# rc_switch_dualsided.net
KiCad netlist of a schematic drawn in EAGLE
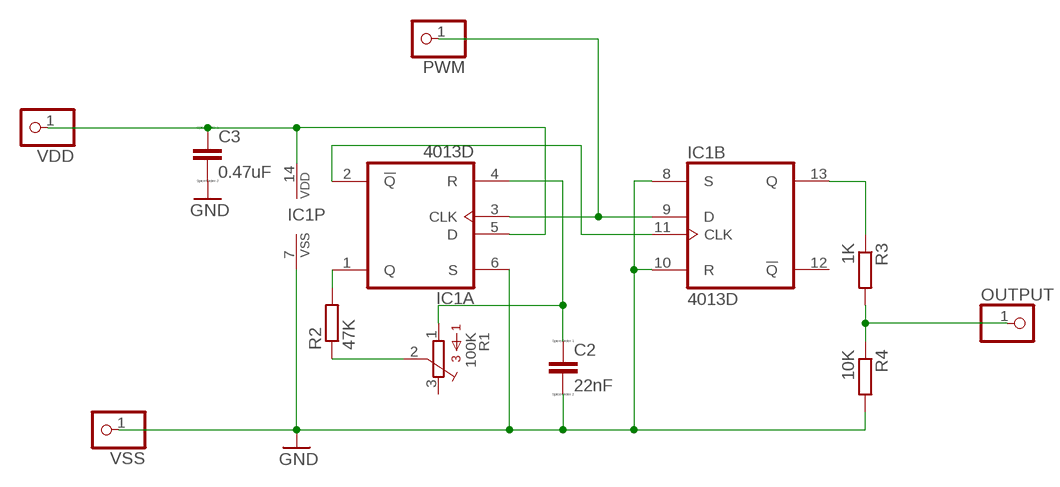
[diagram p0: schematic, sheet 1]

(export (version "E")
  (design (tool "Eeschema 10.0.6"))
  (components
    (comp (ref "C2")
      (value "22nF")
      (footprint "eagle-import:C3216")
      (libsource (lib "eagle-import") (part "CC3216"))
    )
    (comp (ref "C3")
      (value "0.47uF")
      (footprint "eagle-import:C3216")
      (libsource (lib "eagle-import") (part "CC3216"))
    )
    (comp (ref "IC1")
      (value "4013D")
      (footprint "eagle-import:SO14")
      (libsource (lib "eagle-import") (part "4013D"))
    )
    (comp (ref "OUTPUT")
      (value "PINHD-1X1")
      (footprint "eagle-import:1X01")
      (libsource (lib "eagle-import") (part "PINHD-1X1"))
    )
    (comp (ref "PWM")
      (value "PINHD-1X1")
      (footprint "eagle-import:1X01")
      (libsource (lib "eagle-import") (part "PINHD-1X1"))
    )
    (comp (ref "R1")
      (value "100K")
      (footprint "eagle-import:3386P")
      (libsource (lib "eagle-import") (part "3386-P"))
    )
    (comp (ref "R2")
      (value "47K")
      (footprint "eagle-import:R3225")
      (libsource (lib "eagle-import") (part "R-EU_R3225"))
    )
    (comp (ref "R3")
      (value "1K")
      (footprint "eagle-import:R3225")
      (libsource (lib "eagle-import") (part "R-EU_R3225"))
    )
    (comp (ref "R4")
      (value "10K")
      (footprint "eagle-import:R3225")
      (libsource (lib "eagle-import") (part "R-EU_R3225"))
    )
    (comp (ref "VDD")
      (value "PINHD-1X1")
      (footprint "eagle-import:1X01")
      (libsource (lib "eagle-import") (part "PINHD-1X1"))
    )
    (comp (ref "VSS")
      (value "PINHD-1X1")
      (footprint "eagle-import:1X01")
      (libsource (lib "eagle-import") (part "PINHD-1X1"))
    )
  )
  (nets
    (net (code "1") (name "GND") (class "Default")
      (node (ref "C2") (pin "2") (pinfunction "2_2") (pintype "passive"))
      (node (ref "C3") (pin "2") (pinfunction "2_2") (pintype "passive"))
      (node (ref "IC1") (pin "10") (pinfunction "R_10") (pintype "input"))
      (node (ref "IC1") (pin "6") (pinfunction "S_6") (pintype "input"))
      (node (ref "IC1") (pin "7") (pinfunction "VSS_7") (pintype "power_in"))
      (node (ref "IC1") (pin "8") (pinfunction "S_8") (pintype "input"))
      (node (ref "R4") (pin "2") (pinfunction "2_2") (pintype "passive"))
      (node (ref "VSS") (pin "1") (pinfunction "1_1") (pintype "passive"))
    )
    (net (code "2") (name "Net-(IC1A-CLK)") (class "Default")
      (node (ref "IC1") (pin "3") (pinfunction "CLK_3") (pintype "input"))
      (node (ref "IC1") (pin "9") (pinfunction "D_9") (pintype "input"))
      (node (ref "PWM") (pin "1") (pinfunction "1_1") (pintype "passive"))
    )
    (net (code "3") (name "Net-(IC1A-D)") (class "Default")
      (node (ref "C3") (pin "1") (pinfunction "1_1") (pintype "passive"))
      (node (ref "IC1") (pin "14") (pinfunction "VDD_14") (pintype "power_in"))
      (node (ref "IC1") (pin "5") (pinfunction "D_5") (pintype "input"))
      (node (ref "VDD") (pin "1") (pinfunction "1_1") (pintype "passive"))
    )
    (net (code "4") (name "Net-(IC1A-Q)") (class "Default")
      (node (ref "IC1") (pin "1") (pinfunction "Q_1") (pintype "output"))
      (node (ref "R2") (pin "2") (pinfunction "2_2") (pintype "passive"))
    )
    (net (code "5") (name "Net-(IC1A-R)") (class "Default")
      (node (ref "C2") (pin "1") (pinfunction "1_1") (pintype "passive"))
      (node (ref "IC1") (pin "4") (pinfunction "R_4") (pintype "input"))
      (node (ref "R1") (pin "1") (pinfunction "1_1") (pintype "passive"))
    )
    (net (code "6") (name "Net-(IC1A-~{Q})") (class "Default")
      (node (ref "IC1") (pin "11") (pinfunction "CLK_11") (pintype "input"))
      (node (ref "IC1") (pin "2") (pinfunction "~{Q}_2") (pintype "output"))
    )
    (net (code "7") (name "Net-(IC1B-Q)") (class "Default")
      (node (ref "IC1") (pin "13") (pinfunction "Q_13") (pintype "output"))
      (node (ref "R3") (pin "1") (pinfunction "1_1") (pintype "passive"))
    )
    (net (code "8") (name "Net-(OUTPUT-Pad1)") (class "Default")
      (node (ref "OUTPUT") (pin "1") (pinfunction "1_1") (pintype "passive"))
      (node (ref "R3") (pin "2") (pinfunction "2_2") (pintype "passive"))
      (node (ref "R4") (pin "1") (pinfunction "1_1") (pintype "passive"))
    )
    (net (code "9") (name "Net-(R1-Pad2)") (class "Default")
      (node (ref "R1") (pin "2") (pinfunction "2_2") (pintype "passive"))
      (node (ref "R2") (pin "1") (pinfunction "1_1") (pintype "passive"))
    )
    (net (code "10") (name "unconnected-(IC1B-~{Q}-Pad12)") (class "Default")
      (node (ref "IC1") (pin "12") (pinfunction "~{Q}_12") (pintype "output"))
    )
    (net (code "11") (name "unconnected-(R1-Pad3)") (class "Default")
      (node (ref "R1") (pin "3") (pinfunction "3_3") (pintype "passive"))
    )
  )
)
